# QHome.net
KiCad netlist of a schematic drawn in EAGLE
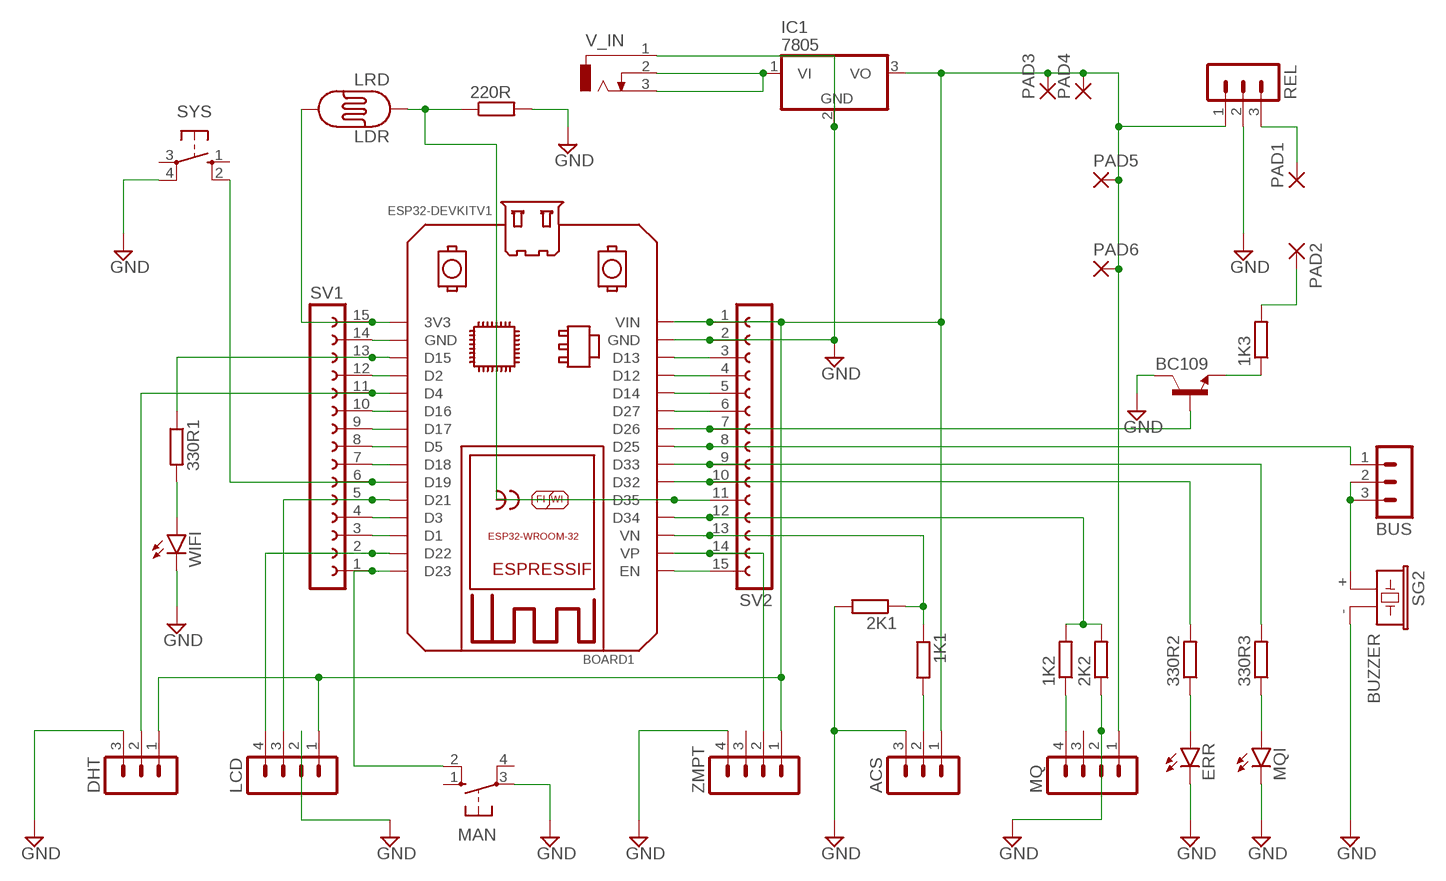
[diagram p0: schematic, sheet 1]

(export (version "E")
  (design (tool "Eeschema 10.0.6"))
  (components
    (comp (ref "1K1")
      (value "R-EU_0207/7")
      (footprint "eagle-import:0207_7")
      (libsource (lib "eagle-import") (part "R-EU_0207/7"))
    )
    (comp (ref "1K2")
      (value "R-EU_0207/7")
      (footprint "eagle-import:0207_7")
      (libsource (lib "eagle-import") (part "R-EU_0207/7"))
    )
    (comp (ref "1K3")
      (value "R-EU_0207/7")
      (footprint "eagle-import:0207_7")
      (libsource (lib "eagle-import") (part "R-EU_0207/7"))
    )
    (comp (ref "2K1")
      (value "R-EU_0207/7")
      (footprint "eagle-import:0207_7")
      (libsource (lib "eagle-import") (part "R-EU_0207/7"))
    )
    (comp (ref "2K2")
      (value "R-EU_0207/7")
      (footprint "eagle-import:0207_7")
      (libsource (lib "eagle-import") (part "R-EU_0207/7"))
    )
    (comp (ref "220R")
      (value "R-EU_0207/7")
      (footprint "eagle-import:0207_7")
      (libsource (lib "eagle-import") (part "R-EU_0207/7"))
    )
    (comp (ref "330R1")
      (value "R-EU_0207/7")
      (footprint "eagle-import:0207_7")
      (libsource (lib "eagle-import") (part "R-EU_0207/7"))
    )
    (comp (ref "330R2")
      (value "R-EU_0207/7")
      (footprint "eagle-import:0207_7")
      (libsource (lib "eagle-import") (part "R-EU_0207/7"))
    )
    (comp (ref "330R3")
      (value "R-EU_0207/7")
      (footprint "eagle-import:0207_7")
      (libsource (lib "eagle-import") (part "R-EU_0207/7"))
    )
    (comp (ref "ACS")
      (value "MA03-1")
      (footprint "eagle-import:MA03-1")
      (libsource (lib "eagle-import") (part "MA03-1"))
    )
    (comp (ref "BC109")
      (value "BF422-NPN-TO92-BCE")
      (footprint "eagle-import:TO92-BCE")
      (libsource (lib "eagle-import") (part "-NPN-TO92-BCEBF422"))
    )
    (comp (ref "BOARD1")
      (value "ESP32DEVKITV1")
      (footprint "eagle-import:ESP32-DEVKITV1")
      (libsource (lib "eagle-import") (part "ESP32DEVKITV1"))
    )
    (comp (ref "BUS")
      (value "MA03-1")
      (footprint "eagle-import:MA03-1")
      (libsource (lib "eagle-import") (part "MA03-1"))
    )
    (comp (ref "DHT")
      (value "MA03-1")
      (footprint "eagle-import:MA03-1")
      (libsource (lib "eagle-import") (part "MA03-1"))
    )
    (comp (ref "ERR")
      (value "LED5MM")
      (footprint "eagle-import:LED5MM")
      (libsource (lib "eagle-import") (part "LED5MM"))
    )
    (comp (ref "IC1")
      (value "7805")
      (footprint "eagle-import:TO220V")
      (libsource (lib "eagle-import") (part "78TV8"))
    )
    (comp (ref "LCD")
      (value "MA04-1")
      (footprint "eagle-import:MA04-1")
      (libsource (lib "eagle-import") (part "MA04-1"))
    )
    (comp (ref "LDR")
      (value "LRD")
      (footprint "eagle-import:ON_BOARD")
      (libsource (lib "eagle-import") (part "PHOTOCELLONB"))
    )
    (comp (ref "MAN")
      (value "10-XX")
      (footprint "eagle-import:B3F-10XX")
      (libsource (lib "eagle-import") (part "10-XX"))
    )
    (comp (ref "MQ")
      (value "MA04-1")
      (footprint "eagle-import:MA04-1")
      (libsource (lib "eagle-import") (part "MA04-1"))
    )
    (comp (ref "MQI")
      (value "LED5MM")
      (footprint "eagle-import:LED5MM")
      (libsource (lib "eagle-import") (part "LED5MM"))
    )
    (comp (ref "PAD1")
      (value "2,54/1,1")
      (footprint "eagle-import:2,54_1,1")
      (libsource (lib "eagle-import") (part "2,54/1,1"))
    )
    (comp (ref "PAD2")
      (value "2,54/1,1")
      (footprint "eagle-import:2,54_1,1")
      (libsource (lib "eagle-import") (part "2,54/1,1"))
    )
    (comp (ref "PAD3")
      (value "2,54/1,1")
      (footprint "eagle-import:2,54_1,1")
      (libsource (lib "eagle-import") (part "2,54/1,1"))
    )
    (comp (ref "PAD4")
      (value "2,54/1,1")
      (footprint "eagle-import:2,54_1,1")
      (libsource (lib "eagle-import") (part "2,54/1,1"))
    )
    (comp (ref "PAD5")
      (value "2,54/1,1")
      (footprint "eagle-import:2,54_1,1")
      (libsource (lib "eagle-import") (part "2,54/1,1"))
    )
    (comp (ref "PAD6")
      (value "2,54/1,1")
      (footprint "eagle-import:2,54_1,1")
      (libsource (lib "eagle-import") (part "2,54/1,1"))
    )
    (comp (ref "REL")
      (value "MA03-1")
      (footprint "eagle-import:MA03-1")
      (libsource (lib "eagle-import") (part "MA03-1"))
    )
    (comp (ref "SG2")
      (value "BUZZER")
      (footprint "eagle-import:F_CM12P")
      (libsource (lib "eagle-import") (part "F/CM12P"))
    )
    (comp (ref "SV1")
      (value "FE15-1")
      (footprint "eagle-import:FE15")
      (libsource (lib "eagle-import") (part "FE15-1"))
    )
    (comp (ref "SV2")
      (value "FE15-1")
      (footprint "eagle-import:FE15")
      (libsource (lib "eagle-import") (part "FE15-1"))
    )
    (comp (ref "SYS")
      (value "10-XX")
      (footprint "eagle-import:B3F-10XX")
      (libsource (lib "eagle-import") (part "10-XX"))
    )
    (comp (ref "V_IN")
      (value "DCJ0303")
      (footprint "eagle-import:DCJ0303")
      (libsource (lib "eagle-import") (part "DCJ0303"))
    )
    (comp (ref "WIFI")
      (value "LED5MM")
      (footprint "eagle-import:LED5MM")
      (libsource (lib "eagle-import") (part "LED5MM"))
    )
    (comp (ref "ZMPT")
      (value "MA04-1")
      (footprint "eagle-import:MA04-1")
      (libsource (lib "eagle-import") (part "MA04-1"))
    )
  )
  (nets
    (net (code "1") (name "GND") (class "Default")
      (node (ref "220R") (pin "2") (pinfunction "2_2") (pintype "passive"))
      (node (ref "2K1") (pin "2") (pinfunction "2_2") (pintype "passive"))
      (node (ref "2K2") (pin "1") (pinfunction "1_1") (pintype "passive"))
      (node (ref "ACS") (pin "3") (pinfunction "3_3") (pintype "passive"))
      (node (ref "BC109") (pin "C") (pinfunction "C_C") (pintype "passive"))
      (node (ref "BOARD1") (pin "GND") (pinfunction "GND_GND") (pintype "bidirectional"))
      (node (ref "DHT") (pin "3") (pinfunction "3_3") (pintype "passive"))
      (node (ref "ERR") (pin "K") (pinfunction "C_K") (pintype "passive"))
      (node (ref "IC1") (pin "2") (pinfunction "GND_2") (pintype "passive"))
      (node (ref "LCD") (pin "2") (pinfunction "2_2") (pintype "passive"))
      (node (ref "MAN") (pin "3") (pinfunction "P_3") (pintype "passive"))
      (node (ref "MQ") (pin "2") (pinfunction "2_2") (pintype "passive"))
      (node (ref "MQI") (pin "K") (pinfunction "C_K") (pintype "passive"))
      (node (ref "REL") (pin "2") (pinfunction "2_2") (pintype "passive"))
      (node (ref "SG2") (pin "-") (pinfunction "2_-") (pintype "passive"))
      (node (ref "SV2") (pin "2") (pinfunction "2_2") (pintype "passive"))
      (node (ref "SYS") (pin "4") (pinfunction "P1_4") (pintype "passive"))
      (node (ref "V_IN") (pin "1") (pinfunction "1_1") (pintype "passive"))
      (node (ref "WIFI") (pin "K") (pinfunction "C_K") (pintype "passive"))
      (node (ref "ZMPT") (pin "4") (pinfunction "4_4") (pintype "passive"))
    )
    (net (code "2") (name "Net-(1K1-Pad1)") (class "Default")
      (node (ref "1K1") (pin "1") (pinfunction "1_1") (pintype "passive"))
      (node (ref "2K1") (pin "1") (pinfunction "1_1") (pintype "passive"))
      (node (ref "BOARD1") (pin "VN") (pinfunction "VN_VN") (pintype "bidirectional"))
      (node (ref "SV2") (pin "13") (pinfunction "13_13") (pintype "passive"))
    )
    (net (code "3") (name "Net-(1K1-Pad2)") (class "Default")
      (node (ref "1K1") (pin "2") (pinfunction "2_2") (pintype "passive"))
      (node (ref "ACS") (pin "2") (pinfunction "2_2") (pintype "passive"))
    )
    (net (code "4") (name "Net-(1K2-Pad1)") (class "Default")
      (node (ref "1K2") (pin "1") (pinfunction "1_1") (pintype "passive"))
      (node (ref "MQ") (pin "4") (pinfunction "4_4") (pintype "passive"))
    )
    (net (code "5") (name "Net-(1K2-Pad2)") (class "Default")
      (node (ref "1K2") (pin "2") (pinfunction "2_2") (pintype "passive"))
      (node (ref "2K2") (pin "2") (pinfunction "2_2") (pintype "passive"))
      (node (ref "BOARD1") (pin "D34") (pinfunction "D34_D34") (pintype "bidirectional"))
      (node (ref "SV2") (pin "12") (pinfunction "12_12") (pintype "passive"))
    )
    (net (code "6") (name "Net-(1K3-Pad1)") (class "Default")
      (node (ref "1K3") (pin "1") (pinfunction "1_1") (pintype "passive"))
      (node (ref "BC109") (pin "E") (pinfunction "E_E") (pintype "passive"))
    )
    (net (code "7") (name "Net-(330R1-Pad1)") (class "Default")
      (node (ref "330R1") (pin "1") (pinfunction "1_1") (pintype "passive"))
      (node (ref "BOARD1") (pin "D15") (pinfunction "D15_D15") (pintype "bidirectional"))
      (node (ref "SV1") (pin "13") (pinfunction "13_13") (pintype "passive"))
    )
    (net (code "8") (name "Net-(330R1-Pad2)") (class "Default")
      (node (ref "330R1") (pin "2") (pinfunction "2_2") (pintype "passive"))
      (node (ref "WIFI") (pin "A") (pinfunction "A_A") (pintype "passive"))
    )
    (net (code "9") (name "Net-(330R2-Pad1)") (class "Default")
      (node (ref "330R2") (pin "1") (pinfunction "1_1") (pintype "passive"))
      (node (ref "ERR") (pin "A") (pinfunction "A_A") (pintype "passive"))
    )
    (net (code "10") (name "Net-(330R2-Pad2)") (class "Default")
      (node (ref "330R2") (pin "2") (pinfunction "2_2") (pintype "passive"))
      (node (ref "BOARD1") (pin "D32") (pinfunction "D32_D32") (pintype "bidirectional"))
      (node (ref "SV2") (pin "10") (pinfunction "10_10") (pintype "passive"))
    )
    (net (code "11") (name "Net-(330R3-Pad1)") (class "Default")
      (node (ref "330R3") (pin "1") (pinfunction "1_1") (pintype "passive"))
      (node (ref "MQI") (pin "A") (pinfunction "A_A") (pintype "passive"))
    )
    (net (code "12") (name "Net-(330R3-Pad2)") (class "Default")
      (node (ref "330R3") (pin "2") (pinfunction "2_2") (pintype "passive"))
      (node (ref "BOARD1") (pin "D33") (pinfunction "D33_D33") (pintype "bidirectional"))
      (node (ref "SV2") (pin "9") (pinfunction "9_9") (pintype "passive"))
    )
    (net (code "13") (name "Net-(BC109-PadB)") (class "Default")
      (node (ref "BC109") (pin "B") (pinfunction "B_B") (pintype "passive"))
      (node (ref "BOARD1") (pin "D26") (pinfunction "D26_D26") (pintype "bidirectional"))
      (node (ref "SV2") (pin "7") (pinfunction "7_7") (pintype "passive"))
    )
    (net (code "14") (name "Net-(BOARD1-GND-PadGND@1)") (class "Default")
      (node (ref "BOARD1") (pin "GND@1") (pinfunction "GND_GND@1") (pintype "bidirectional"))
      (node (ref "SV1") (pin "14") (pinfunction "14_14") (pintype "passive"))
    )
    (net (code "15") (name "Net-(BOARD1-PadD1)") (class "Default")
      (node (ref "BOARD1") (pin "D1") (pinfunction "D1_D1") (pintype "bidirectional"))
      (node (ref "SV1") (pin "3") (pinfunction "3_3") (pintype "passive"))
    )
    (net (code "16") (name "Net-(BOARD1-PadD2)") (class "Default")
      (node (ref "BOARD1") (pin "D2") (pinfunction "D2_D2") (pintype "bidirectional"))
      (node (ref "SV1") (pin "12") (pinfunction "12_12") (pintype "passive"))
    )
    (net (code "17") (name "Net-(BOARD1-PadD3)") (class "Default")
      (node (ref "BOARD1") (pin "D3") (pinfunction "D3_D3") (pintype "bidirectional"))
      (node (ref "SV1") (pin "4") (pinfunction "4_4") (pintype "passive"))
    )
    (net (code "18") (name "Net-(BOARD1-PadD4)") (class "Default")
      (node (ref "BOARD1") (pin "D4") (pinfunction "D4_D4") (pintype "bidirectional"))
      (node (ref "DHT") (pin "2") (pinfunction "2_2") (pintype "passive"))
      (node (ref "SV1") (pin "11") (pinfunction "11_11") (pintype "passive"))
    )
    (net (code "19") (name "Net-(BOARD1-PadD5)") (class "Default")
      (node (ref "BOARD1") (pin "D5") (pinfunction "D5_D5") (pintype "bidirectional"))
      (node (ref "SV1") (pin "8") (pinfunction "8_8") (pintype "passive"))
    )
    (net (code "20") (name "Net-(BOARD1-PadD12)") (class "Default")
      (node (ref "BOARD1") (pin "D12") (pinfunction "D12_D12") (pintype "bidirectional"))
      (node (ref "SV2") (pin "4") (pinfunction "4_4") (pintype "passive"))
    )
    (net (code "21") (name "Net-(BOARD1-PadD13)") (class "Default")
      (node (ref "BOARD1") (pin "D13") (pinfunction "D13_D13") (pintype "bidirectional"))
      (node (ref "SV2") (pin "3") (pinfunction "3_3") (pintype "passive"))
    )
    (net (code "22") (name "Net-(BOARD1-PadD14)") (class "Default")
      (node (ref "BOARD1") (pin "D14") (pinfunction "D14_D14") (pintype "bidirectional"))
      (node (ref "SV2") (pin "5") (pinfunction "5_5") (pintype "passive"))
    )
    (net (code "23") (name "Net-(BOARD1-PadD16)") (class "Default")
      (node (ref "BOARD1") (pin "D16") (pinfunction "D16_D16") (pintype "bidirectional"))
      (node (ref "SV1") (pin "10") (pinfunction "10_10") (pintype "passive"))
    )
    (net (code "24") (name "Net-(BOARD1-PadD17)") (class "Default")
      (node (ref "BOARD1") (pin "D17") (pinfunction "D17_D17") (pintype "bidirectional"))
      (node (ref "SV1") (pin "9") (pinfunction "9_9") (pintype "passive"))
    )
    (net (code "25") (name "Net-(BOARD1-PadD18)") (class "Default")
      (node (ref "BOARD1") (pin "D18") (pinfunction "D18_D18") (pintype "bidirectional"))
      (node (ref "SV1") (pin "7") (pinfunction "7_7") (pintype "passive"))
    )
    (net (code "26") (name "Net-(BOARD1-PadD21)") (class "Default")
      (node (ref "BOARD1") (pin "D21") (pinfunction "D21_D21") (pintype "bidirectional"))
      (node (ref "LCD") (pin "3") (pinfunction "3_3") (pintype "passive"))
      (node (ref "SV1") (pin "5") (pinfunction "5_5") (pintype "passive"))
    )
    (net (code "27") (name "Net-(BOARD1-PadD22)") (class "Default")
      (node (ref "BOARD1") (pin "D22") (pinfunction "D22_D22") (pintype "bidirectional"))
      (node (ref "LCD") (pin "4") (pinfunction "4_4") (pintype "passive"))
      (node (ref "SV1") (pin "2") (pinfunction "2_2") (pintype "passive"))
    )
    (net (code "28") (name "Net-(BOARD1-PadD25)") (class "Default")
      (node (ref "BOARD1") (pin "D25") (pinfunction "D25_D25") (pintype "bidirectional"))
      (node (ref "BUS") (pin "1") (pinfunction "1_1") (pintype "passive"))
      (node (ref "SV2") (pin "8") (pinfunction "8_8") (pintype "passive"))
    )
    (net (code "29") (name "Net-(BOARD1-PadD27)") (class "Default")
      (node (ref "BOARD1") (pin "D27") (pinfunction "D27_D27") (pintype "bidirectional"))
      (node (ref "SV2") (pin "6") (pinfunction "6_6") (pintype "passive"))
    )
    (net (code "30") (name "Net-(BOARD1-PadEN)") (class "Default")
      (node (ref "BOARD1") (pin "EN") (pinfunction "EN_EN") (pintype "bidirectional"))
      (node (ref "SV2") (pin "15") (pinfunction "15_15") (pintype "passive"))
    )
    (net (code "31") (name "Net-(BOARD1-PadVP)") (class "Default")
      (node (ref "BOARD1") (pin "VP") (pinfunction "VP_VP") (pintype "bidirectional"))
      (node (ref "SV2") (pin "14") (pinfunction "14_14") (pintype "passive"))
      (node (ref "ZMPT") (pin "2") (pinfunction "2_2") (pintype "passive"))
    )
    (net (code "32") (name "Net-(IC1-VI)") (class "Default")
      (node (ref "IC1") (pin "1") (pinfunction "VI_1") (pintype "input"))
      (node (ref "V_IN") (pin "2") (pinfunction "2_2") (pintype "passive"))
      (node (ref "V_IN") (pin "3") (pinfunction "3_3") (pintype "passive"))
    )
    (net (code "33") (name "Net-(IC1-VO)") (class "Default")
      (node (ref "ACS") (pin "1") (pinfunction "1_1") (pintype "passive"))
      (node (ref "BOARD1") (pin "VIN") (pinfunction "VIN_VIN") (pintype "bidirectional"))
      (node (ref "DHT") (pin "1") (pinfunction "1_1") (pintype "passive"))
      (node (ref "IC1") (pin "3") (pinfunction "VO_3") (pintype "passive"))
      (node (ref "LCD") (pin "1") (pinfunction "1_1") (pintype "passive"))
      (node (ref "MQ") (pin "1") (pinfunction "1_1") (pintype "passive"))
      (node (ref "PAD3") (pin "1") (pinfunction "P_1") (pintype "passive"))
      (node (ref "PAD4") (pin "1") (pinfunction "P_1") (pintype "passive"))
      (node (ref "PAD5") (pin "1") (pinfunction "P_1") (pintype "passive"))
      (node (ref "PAD6") (pin "1") (pinfunction "P_1") (pintype "passive"))
      (node (ref "REL") (pin "1") (pinfunction "1_1") (pintype "passive"))
      (node (ref "SV2") (pin "1") (pinfunction "1_1") (pintype "passive"))
      (node (ref "ZMPT") (pin "1") (pinfunction "1_1") (pintype "passive"))
    )
    (net (code "34") (name "Net-(LDR-P$1)") (class "Default")
      (node (ref "220R") (pin "1") (pinfunction "1_1") (pintype "passive"))
      (node (ref "BOARD1") (pin "D35") (pinfunction "D35_D35") (pintype "bidirectional"))
      (node (ref "LDR") (pin "1") (pinfunction "P$1_1") (pintype "bidirectional"))
      (node (ref "SV2") (pin "11") (pinfunction "11_11") (pintype "passive"))
    )
    (net (code "35") (name "Net-(LDR-P$2)") (class "Default")
      (node (ref "BOARD1") (pin "3V3") (pinfunction "3V3_3V3") (pintype "bidirectional"))
      (node (ref "LDR") (pin "2") (pinfunction "P$2_2") (pintype "bidirectional"))
      (node (ref "SV1") (pin "15") (pinfunction "15_15") (pintype "passive"))
    )
    (net (code "36") (name "Net-(MAN-S1)") (class "Default")
      (node (ref "BOARD1") (pin "D23") (pinfunction "D23_D23") (pintype "bidirectional"))
      (node (ref "MAN") (pin "2") (pinfunction "S1_2") (pintype "passive"))
      (node (ref "SV1") (pin "1") (pinfunction "1_1") (pintype "passive"))
    )
    (net (code "37") (name "Net-(PAD1-P)") (class "Default")
      (node (ref "PAD1") (pin "1") (pinfunction "P_1") (pintype "passive"))
      (node (ref "REL") (pin "3") (pinfunction "3_3") (pintype "passive"))
    )
    (net (code "38") (name "Net-(PAD2-P)") (class "Default")
      (node (ref "1K3") (pin "2") (pinfunction "2_2") (pintype "passive"))
      (node (ref "PAD2") (pin "1") (pinfunction "P_1") (pintype "passive"))
    )
    (net (code "39") (name "Net-(SG2-1)") (class "Default")
      (node (ref "BUS") (pin "2") (pinfunction "2_2") (pintype "passive"))
      (node (ref "BUS") (pin "3") (pinfunction "3_3") (pintype "passive"))
      (node (ref "SG2") (pin "+") (pinfunction "1_+") (pintype "passive"))
    )
    (net (code "40") (name "Net-(SYS-S1)") (class "Default")
      (node (ref "BOARD1") (pin "D19") (pinfunction "D19_D19") (pintype "bidirectional"))
      (node (ref "SV1") (pin "6") (pinfunction "6_6") (pintype "passive"))
      (node (ref "SYS") (pin "2") (pinfunction "S1_2") (pintype "passive"))
    )
    (net (code "41") (name "unconnected-(MAN-P1-Pad4)") (class "Default")
      (node (ref "MAN") (pin "4") (pinfunction "P1_4") (pintype "passive"))
    )
    (net (code "42") (name "unconnected-(MAN-S-Pad1)") (class "Default")
      (node (ref "MAN") (pin "1") (pinfunction "S_1") (pintype "passive"))
    )
    (net (code "43") (name "unconnected-(MQ-Pad3)") (class "Default")
      (node (ref "MQ") (pin "3") (pinfunction "3_3") (pintype "passive"))
    )
    (net (code "44") (name "unconnected-(SYS-P-Pad3)") (class "Default")
      (node (ref "SYS") (pin "3") (pinfunction "P_3") (pintype "passive"))
    )
    (net (code "45") (name "unconnected-(SYS-S-Pad1)") (class "Default")
      (node (ref "SYS") (pin "1") (pinfunction "S_1") (pintype "passive"))
    )
    (net (code "46") (name "unconnected-(ZMPT-Pad3)") (class "Default")
      (node (ref "ZMPT") (pin "3") (pinfunction "3_3") (pintype "passive"))
    )
  )
)
